# Sheet_1_2025-06-27.net
KiCad netlist of a schematic drawn in Altium Designer
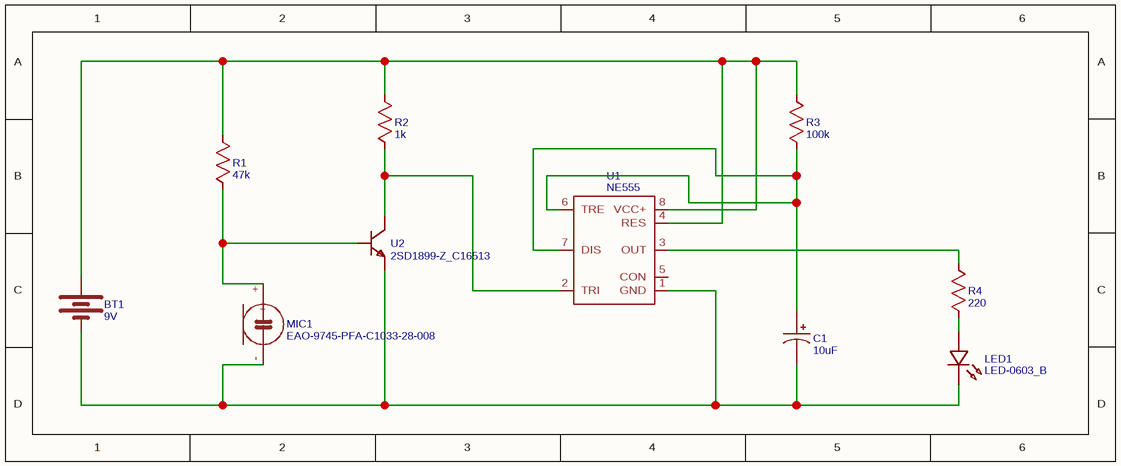
[diagram p0: Sheet_1_2025-06-27.schdoc]

(export (version "E")
  (design (tool "Eeschema 10.0.6"))
  (components
    (comp (ref "BT1")
      (value "9V")
      (fields
        (field (name "MANUFACTURER") "Q&J")
        (field (name "MANUFACTURER PART") "9V电池铜线扣 铜100mm")
        (field (name "CONTRIBUTOR") "lcsc")
      )
      (libsource (lib "altium-import") (part "root_3_9V_"))
    )
    (comp (ref "C1")
      (value "10uF")
      (fields (field (name "CONTRIBUTOR") "LCEDA_Lib"))
      (libsource (lib "altium-import") (part "root_3_10uF_"))
    )
    (comp (ref "LED1")
      (value "LED-0603_B")
      (fields
        (field (name "MANUFACTURER") "EVERLIGHT(台湾亿光)")
        (field (name "MANUFACTURER PART") "19-217/BHC-ZL1M2RY/3T")
        (field (name "CONTRIBUTOR") "LCEDA_01")
      )
      (libsource (lib "altium-import") (part "root_3_LED-0603_B_"))
    )
    (comp (ref "MIC1")
      (value "EAO-9745-PFA-C1033-28-008")
      (description "Mini Microphone")
      (libsource (lib "altium-import") (part "root_0_EAO-9745-PFA-C1033-28-008_"))
    )
    (comp (ref "R1")
      (value "47k")
      (fields (field (name "CONTRIBUTOR") "LCEDA_Lib"))
      (libsource (lib "altium-import") (part "root_1_47k_"))
    )
    (comp (ref "R2")
      (value "1k")
      (fields (field (name "CONTRIBUTOR") "LCEDA_Lib"))
      (libsource (lib "altium-import") (part "root_1_1k_"))
    )
    (comp (ref "R3")
      (value "100k")
      (fields (field (name "CONTRIBUTOR") "LCEDA_Lib"))
      (libsource (lib "altium-import") (part "root_1_100k_"))
    )
    (comp (ref "R4")
      (value "220")
      (fields (field (name "CONTRIBUTOR") "LCEDA_Lib"))
      (libsource (lib "altium-import") (part "root_1_220_"))
    )
    (comp (ref "U1")
      (value "NE555")
      (fields (field (name "CONTRIBUTOR") "SparkFun"))
      (libsource (lib "altium-import") (part "root_0_NE555_"))
    )
    (comp (ref "U2")
      (value "2SD1899-Z_C16513")
      (fields
        (field (name "MANUFACTURER") "CJ")
        (field (name "MANUFACTURER PART") "2SD1899-Z")
        (field (name "CONTRIBUTOR") "LCSC")
      )
      (libsource (lib "altium-import") (part "root_0_2SD1899-Z_C16513_"))
    )
  )
  (nets
    (net (code "1") (name "Net-(BT1-+)") (class "Default")
      (node (ref "BT1") (pin "1") (pinfunction "+_1") (pintype "passive"))
      (node (ref "R1") (pin "2") (pinfunction "2_2") (pintype "passive"))
      (node (ref "R2") (pin "2") (pinfunction "2_2") (pintype "passive"))
      (node (ref "R3") (pin "2") (pinfunction "2_2") (pintype "passive"))
      (node (ref "U1") (pin "4") (pinfunction "RES_4") (pintype "passive"))
      (node (ref "U1") (pin "8") (pinfunction "VCC+_8") (pintype "passive"))
    )
    (net (code "2") (name "Net-(BT1--)") (class "Default")
      (node (ref "BT1") (pin "2") (pinfunction "-_2") (pintype "passive"))
      (node (ref "C1") (pin "2") (pinfunction "2_2") (pintype "passive"))
      (node (ref "LED1") (pin "2") (pinfunction "2_2") (pintype "passive"))
      (node (ref "MIC1") (pin "-") (pinfunction "-_-") (pintype "passive"))
      (node (ref "U1") (pin "1") (pinfunction "GND_1") (pintype "passive"))
      (node (ref "U2") (pin "3") (pinfunction "E_3") (pintype "passive"))
    )
    (net (code "3") (name "Net-(LED1-Pad1)") (class "Default")
      (node (ref "LED1") (pin "1") (pinfunction "1_1") (pintype "passive"))
      (node (ref "R4") (pin "1") (pinfunction "1_1") (pintype "passive"))
    )
    (net (code "4") (name "Net-(U1-DIS)") (class "Default")
      (node (ref "C1") (pin "1") (pinfunction "1_1") (pintype "passive"))
      (node (ref "R3") (pin "1") (pinfunction "1_1") (pintype "passive"))
      (node (ref "U1") (pin "6") (pinfunction "TRE_6") (pintype "passive"))
      (node (ref "U1") (pin "7") (pinfunction "DIS_7") (pintype "passive"))
    )
    (net (code "5") (name "Net-(U1-OUT)") (class "Default")
      (node (ref "R4") (pin "2") (pinfunction "2_2") (pintype "passive"))
      (node (ref "U1") (pin "3") (pinfunction "OUT_3") (pintype "passive"))
    )
    (net (code "6") (name "Net-(U1-TRI)") (class "Default")
      (node (ref "R2") (pin "1") (pinfunction "1_1") (pintype "passive"))
      (node (ref "U1") (pin "2") (pinfunction "TRI_2") (pintype "passive"))
      (node (ref "U2") (pin "2") (pinfunction "C_2") (pintype "passive"))
    )
    (net (code "7") (name "Net-(U2-B)") (class "Default")
      (node (ref "MIC1") (pin "+") (pinfunction "+_+") (pintype "passive"))
      (node (ref "R1") (pin "1") (pinfunction "1_1") (pintype "passive"))
      (node (ref "U2") (pin "1") (pinfunction "B_1") (pintype "passive"))
    )
    (net (code "8") (name "unconnected-(U1-CON-Pad5)") (class "Default")
      (node (ref "U1") (pin "5") (pinfunction "CON_5") (pintype "passive"))
    )
  )
)
